# FULL_CB_Power_REV_C.net
KiCad netlist of a schematic drawn in Altium Designer
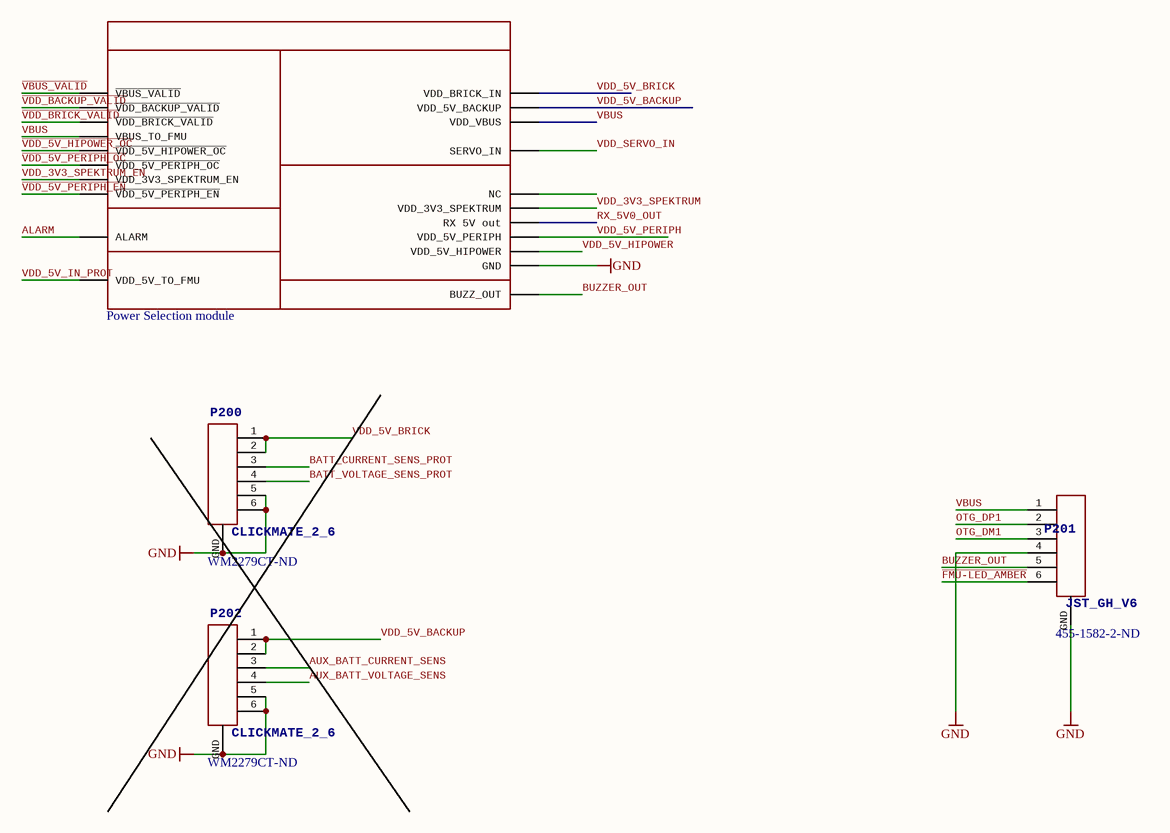
[diagram p0: FULL_CB_Power_REV_C.SchDoc]

(export (version "E")
  (design (tool "Eeschema 10.0.6"))
  (components
    (comp (ref "P200")
      (value "CLICKMATE_2_6")
      (footprint "CLICKMATE_V6_2MM")
      (description "Connector, Header, 6Pos, 2.54MM, Vert, THT, Au")
      (fields (field (name "SUPPLIER PART NUMBER 1") "WM2279CT-ND"))
      (libsource (lib "CB_REV_C") (part "CLICKMATE_2_6"))
    )
    (comp (ref "P201")
      (value "JST_GH_V6")
      (footprint "JST_GH_V6")
      (description "BM06B-GHS-TBT")
      (fields (field (name "SUPPLIER PART NUMBER 1") "455-1582-2-ND"))
      (libsource (lib "CB_REV_C") (part "JST_GH_V6"))
    )
    (comp (ref "P202")
      (value "CLICKMATE_2_6")
      (footprint "CLICKMATE_V6_2MM")
      (description "Connector, Header, 6Pos, 2.54MM, Vert, THT, Au")
      (fields (field (name "SUPPLIER PART NUMBER 1") "WM2279CT-ND"))
      (libsource (lib "CB_REV_C") (part "CLICKMATE_2_6"))
    )
    (comp (ref "PSM200")
      (value "Power Selection module")
      (footprint "PSM")
      (description "PCA, PSM, Assembly")
      (libsource (lib "CB_REV_C") (part "PSMPSM"))
    )
  )
  (nets
    (net (code "1") (name "/ALARM") (class "Default")
      (node (ref "PSM200") (pin "ALARM") (pinfunction "ALARM_ALARM") (pintype "passive"))
    )
    (net (code "2") (name "/AUX_BATT_CURRENT_SENS") (class "Default")
      (node (ref "P202") (pin "3") (pinfunction "3_3") (pintype "passive"))
    )
    (net (code "3") (name "/AUX_BATT_VOLTAGE_SENS") (class "Default")
      (node (ref "P202") (pin "4") (pinfunction "4_4") (pintype "passive"))
    )
    (net (code "4") (name "/BATT_CURRENT_SENS_PROT") (class "Default")
      (node (ref "P200") (pin "3") (pinfunction "3_3") (pintype "passive"))
    )
    (net (code "5") (name "/BATT_VOLTAGE_SENS_PROT") (class "Default")
      (node (ref "P200") (pin "4") (pinfunction "4_4") (pintype "passive"))
    )
    (net (code "6") (name "/BUZZER_OUT") (class "Default")
      (node (ref "P201") (pin "5") (pinfunction "5_5") (pintype "passive"))
      (node (ref "PSM200") (pin "BUZZER_OUT") (pinfunction "BUZZ_OUT_BUZZER_OUT") (pintype "passive"))
    )
    (net (code "7") (name "/OTG_DM1") (class "Default")
      (node (ref "P201") (pin "3") (pinfunction "3_3") (pintype "passive"))
    )
    (net (code "8") (name "/OTG_DP1") (class "Default")
      (node (ref "P201") (pin "2") (pinfunction "2_2") (pintype "passive"))
    )
    (net (code "9") (name "/RX_5V0_OUT") (class "Default")
      (node (ref "PSM200") (pin "RX") (pinfunction "RX_5V_out_RX") (pintype "passive"))
    )
    (net (code "10") (name "/VBUS") (class "Default")
      (node (ref "P201") (pin "1") (pinfunction "1_1") (pintype "passive"))
      (node (ref "PSM200") (pin "VBUS") (pinfunction "VBUS_TO_FMU_VBUS") (pintype "passive"))
      (node (ref "PSM200") (pin "VDD_VBUS") (pinfunction "VDD_VBUS_VDD_VBUS") (pintype "passive"))
    )
    (net (code "11") (name "/VDD_3V3_SPEKTRUM") (class "Default")
      (node (ref "PSM200") (pin "SPEK") (pinfunction "VDD_3V3_SPEKTRUM_SPEK") (pintype "passive"))
    )
    (net (code "12") (name "/VDD_3V3_SPEKTRUM_EN") (class "Default")
      (node (ref "PSM200") (pin "VDD_3V3_SPEKTRUM_EN") (pinfunction "VDD_3V3_SPEKTRUM_EN_VDD_3V3_SPEKTRUM_EN") (pintype "passive"))
    )
    (net (code "13") (name "/VDD_5V_BACKUP") (class "Default")
      (node (ref "P202") (pin "1") (pinfunction "1_1") (pintype "passive"))
      (node (ref "P202") (pin "2") (pinfunction "2_2") (pintype "passive"))
      (node (ref "PSM200") (pin "VDD_5V_BACKUP") (pinfunction "VDD_5V_BACKUP_VDD_5V_BACKUP") (pintype "passive"))
    )
    (net (code "14") (name "/VDD_5V_BRICK") (class "Default")
      (node (ref "P200") (pin "1") (pinfunction "1_1") (pintype "passive"))
      (node (ref "P200") (pin "2") (pinfunction "2_2") (pintype "passive"))
      (node (ref "PSM200") (pin "VDD_BRICK_IN") (pinfunction "VDD_BRICK_IN_VDD_BRICK_IN") (pintype "passive"))
    )
    (net (code "15") (name "/VDD_5V_HIPOWER") (class "Default")
      (node (ref "PSM200") (pin "5V_HIPOWER") (pinfunction "VDD_5V_HIPOWER_5V_HIPOWER") (pintype "passive"))
    )
    (net (code "16") (name "/VDD_5V_IN_PROT") (class "Default")
      (node (ref "PSM200") (pin "VDD_5V_IN_PROT") (pinfunction "VDD_5V_TO_FMU_VDD_5V_IN_PROT") (pintype "passive"))
    )
    (net (code "17") (name "/VDD_5V_PERIPH") (class "Default")
      (node (ref "PSM200") (pin "5V_PERIPH") (pinfunction "VDD_5V_PERIPH_5V_PERIPH") (pintype "passive"))
    )
    (net (code "18") (name "/VDD_SERVO_IN") (class "Default")
      (node (ref "PSM200") (pin "SERVO_IN") (pinfunction "SERVO_IN_SERVO_IN") (pintype "passive"))
    )
    (net (code "19") (name "/~{FMU-LED_AMBER}") (class "Default")
      (node (ref "P201") (pin "6") (pinfunction "6_6") (pintype "passive"))
    )
    (net (code "20") (name "/~{VBUS_VALID}") (class "Default")
      (node (ref "PSM200") (pin "!VBUS_VALID") (pinfunction "~{VBUS_VALID}_!VBUS_VALID") (pintype "passive"))
    )
    (net (code "21") (name "/~{VDD_5V_HIPOWER_OC}") (class "Default")
      (node (ref "PSM200") (pin "!VDD_5V_HIPOWER_OC") (pinfunction "~{VDD_5V_HIPOWER_OC}_!VDD_5V_HIPOWER_OC") (pintype "passive"))
    )
    (net (code "22") (name "/~{VDD_5V_PERIPH_EN}") (class "Default")
      (node (ref "PSM200") (pin "!VDD_5V_PERIPH_EN") (pinfunction "~{VDD_5V_PERIPH_EN}_!VDD_5V_PERIPH_EN") (pintype "passive"))
    )
    (net (code "23") (name "/~{VDD_5V_PERIPH_OC}") (class "Default")
      (node (ref "PSM200") (pin "!VDD_5V_PERIPH_OC") (pinfunction "~{VDD_5V_PERIPH_OC}_!VDD_5V_PERIPH_OC") (pintype "passive"))
    )
    (net (code "24") (name "/~{VDD_BACKUP_VALID}") (class "Default")
      (node (ref "PSM200") (pin "!VDD_BACKUP_VALID") (pinfunction "~{VDD_BACKUP_VALID}_!VDD_BACKUP_VALID") (pintype "passive"))
    )
    (net (code "25") (name "/~{VDD_BRICK_VALID}") (class "Default")
      (node (ref "PSM200") (pin "!VDD_BRICK_VALID") (pinfunction "~{VDD_BRICK_VALID}_!VDD_BRICK_VALID") (pintype "passive"))
    )
    (net (code "26") (name "GND") (class "Default")
      (node (ref "P200") (pin "5") (pinfunction "5_5") (pintype "passive"))
      (node (ref "P200") (pin "6") (pinfunction "6_6") (pintype "passive"))
      (node (ref "P200") (pin "GND") (pinfunction "GND_GND") (pintype "passive"))
      (node (ref "P201") (pin "4") (pinfunction "4_4") (pintype "passive"))
      (node (ref "P201") (pin "GND") (pinfunction "GND_GND") (pintype "passive"))
      (node (ref "P202") (pin "5") (pinfunction "5_5") (pintype "passive"))
      (node (ref "P202") (pin "6") (pinfunction "6_6") (pintype "passive"))
      (node (ref "P202") (pin "GND") (pinfunction "GND_GND") (pintype "passive"))
      (node (ref "PSM200") (pin "GND") (pinfunction "GND_GND") (pintype "passive"))
    )
    (net (code "27") (name "unconnected-(PSM200-PadNC)") (class "Default")
      (node (ref "PSM200") (pin "NC") (pinfunction "NC_NC") (pintype "passive"))
    )
  )
)
